# hot_air.net
KiCad netlist of a schematic drawn in Altium Designer
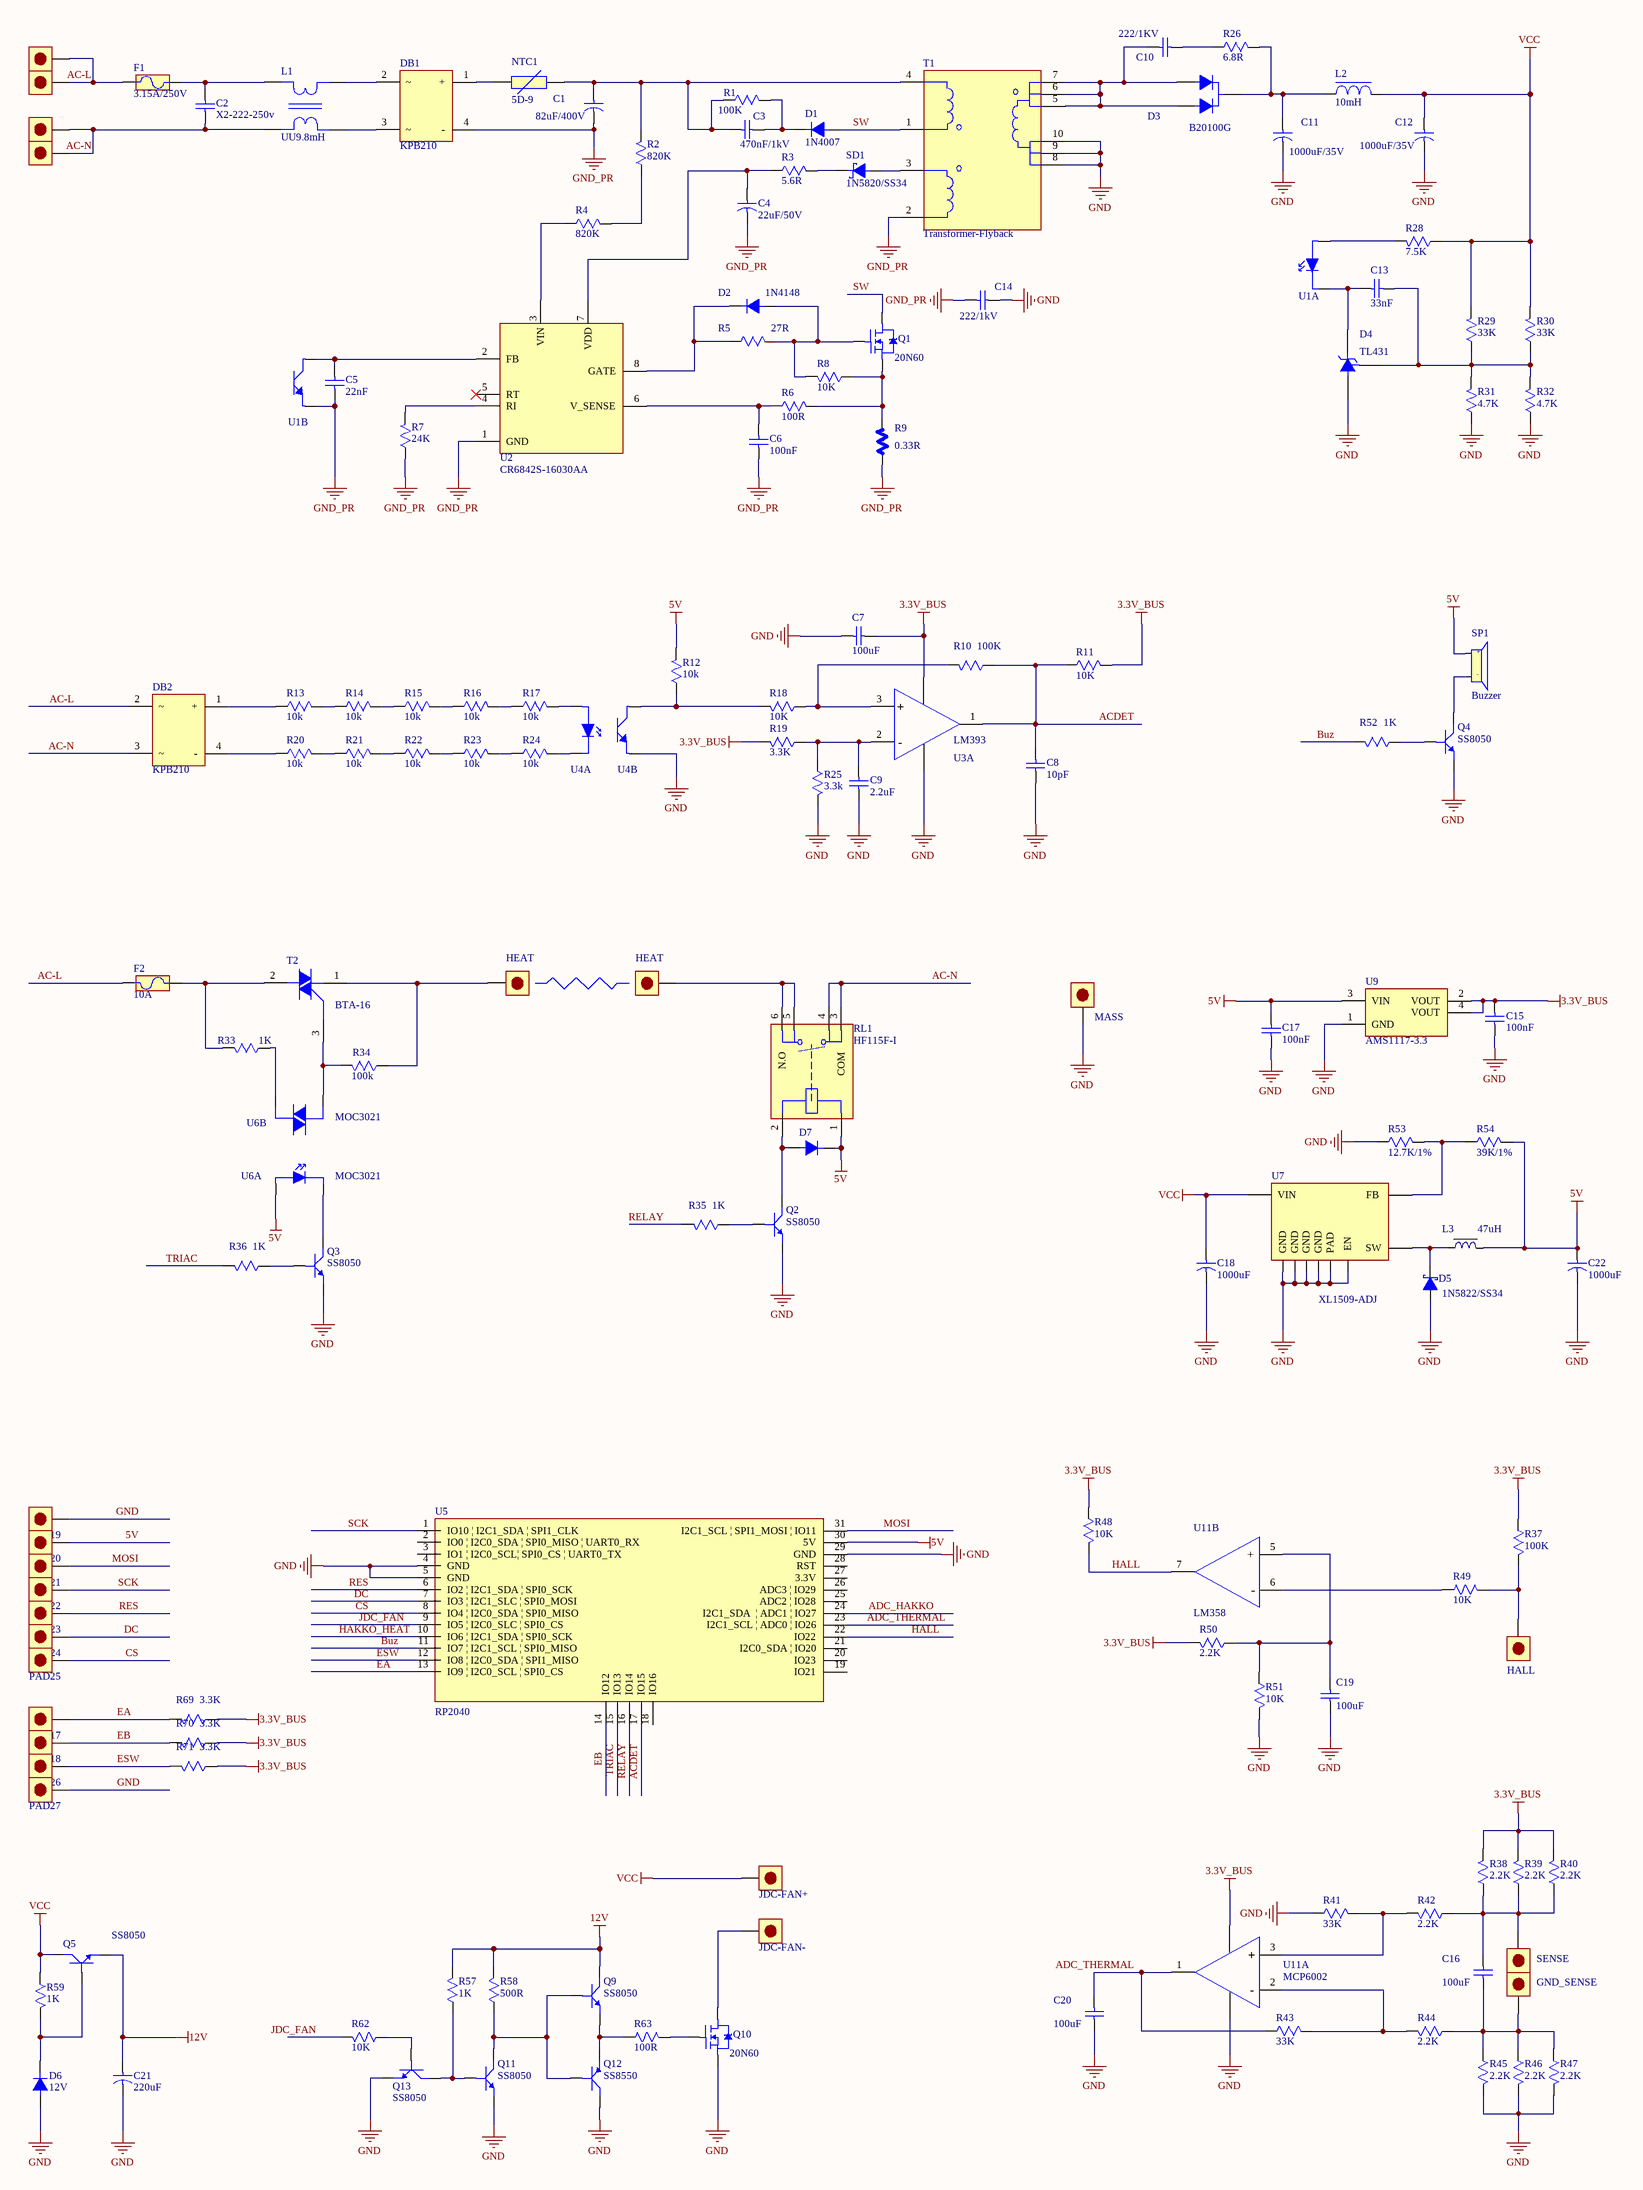
[diagram p0: hot_air.SchDoc]

(export (version "E")
  (design (tool "Eeschema 10.0.6"))
  (components
    (comp (ref "C1")
      (value "82uF/400V")
      (footprint "CAP-TH-16MM")
      (libsource (lib "Huan_basic") (part "Capacitor_polar"))
    )
    (comp (ref "C2")
      (value "X2-222-250v")
      (footprint "CAPACITOR-X2_10MM")
      (libsource (lib "Huan_basic") (part "Capacitor_non-polar"))
    )
    (comp (ref "C3")
      (value "470nF/1kV")
      (footprint "CAP-HV")
      (libsource (lib "Huan_basic") (part "Capacitor_non-polar"))
    )
    (comp (ref "C4")
      (value "22uF/50V")
      (footprint "CAP-TH-6.3MM")
      (libsource (lib "Huan_basic") (part "Capacitor_polar"))
    )
    (comp (ref "C5")
      (value "22nF")
      (footprint "C0805")
      (libsource (lib "Huan_basic") (part "Capacitor_non-polar"))
    )
    (comp (ref "C6")
      (value "100nF")
      (footprint "C0805")
      (libsource (lib "Huan_basic") (part "Capacitor_non-polar"))
    )
    (comp (ref "C7")
      (value "100uF")
      (footprint "C0805")
      (libsource (lib "Huan_basic") (part "Capacitor_non-polar"))
    )
    (comp (ref "C8")
      (value "10pF")
      (footprint "C0805")
      (libsource (lib "Huan_basic") (part "Capacitor_non-polar"))
    )
    (comp (ref "C9")
      (value "2.2uF")
      (footprint "C0805")
      (libsource (lib "Huan_basic") (part "Capacitor_non-polar"))
    )
    (comp (ref "C10")
      (value "222/1KV")
      (footprint "CAP-HV")
      (libsource (lib "Huan_basic") (part "Capacitor_non-polar"))
    )
    (comp (ref "C11")
      (value "1000uF/35V")
      (footprint "CAP-TH-10MM")
      (libsource (lib "Huan_basic") (part "Capacitor_polar"))
    )
    (comp (ref "C12")
      (value "1000uF/35V")
      (footprint "CAP-TH-10MM")
      (libsource (lib "Huan_basic") (part "Capacitor_polar"))
    )
    (comp (ref "C13")
      (value "33nF")
      (footprint "C0805")
      (libsource (lib "Huan_basic") (part "Capacitor_non-polar"))
    )
    (comp (ref "C14")
      (value "222/1kV")
      (footprint "CAP-HV")
      (libsource (lib "Huan_basic") (part "Capacitor_non-polar"))
    )
    (comp (ref "C15")
      (value "100nF")
      (footprint "C0805")
      (libsource (lib "Huan_basic") (part "Capacitor_non-polar"))
    )
    (comp (ref "C16")
      (value "100uF")
      (footprint "C0805")
      (libsource (lib "Huan_basic") (part "Capacitor_non-polar"))
    )
    (comp (ref "C17")
      (value "100nF")
      (footprint "C1206")
      (libsource (lib "Huan_basic") (part "Capacitor_non-polar"))
    )
    (comp (ref "C18")
      (value "1000uF")
      (footprint "CAP-TH-8MM")
      (libsource (lib "Huan_basic") (part "Capacitor_polar"))
    )
    (comp (ref "C19")
      (value "100uF")
      (footprint "C0805")
      (libsource (lib "Huan_basic") (part "Capacitor_non-polar"))
    )
    (comp (ref "C20")
      (value "100uF")
      (footprint "C0805")
      (libsource (lib "Huan_basic") (part "Capacitor_non-polar"))
    )
    (comp (ref "C21")
      (value "220uF")
      (footprint "CAP-TH-10MM")
      (libsource (lib "Huan_basic") (part "Capacitor_polar"))
    )
    (comp (ref "C22")
      (value "1000uF")
      (footprint "CAP-TH-8MM")
      (libsource (lib "Huan_basic") (part "Capacitor_polar"))
    )
    (comp (ref "D1")
      (value "1N4007")
      (footprint "DIODE/POW/1A")
      (libsource (lib "Huan_basic") (part "Diode"))
    )
    (comp (ref "D2")
      (value "1N4148")
      (footprint "LL-34(MiniMELF)")
      (libsource (lib "Huan_basic") (part "Diode"))
    )
    (comp (ref "D3") (value "B20100G") (footprint "TO-220") (libsource (lib "Huan_basic") (part "Diode-HC")))
    (comp (ref "D4") (value "TL431") (footprint "SOT-23") (libsource (lib "Huan_basic") (part "TL431")))
    (comp (ref "D5")
      (value "1N5822/SS34")
      (footprint "DO-214AC(SMA)")
      (description "Diode  Schottky")
      (libsource (lib "Sang_Library") (part "Diode  Schottky"))
    )
    (comp (ref "D6") (value "12V") (footprint "DO-41_V") (libsource (lib "Huan_basic") (part "Diode")))
    (comp (ref "D7") (value "~") (footprint "SOD-123F") (libsource (lib "Huan_basic") (part "Diode")))
    (comp (ref "DB1") (value "KPB210") (footprint "KBP210") (libsource (lib "Huan_basic") (part "H-Bridge")))
    (comp (ref "DB2") (value "KPB210") (footprint "ABS210") (libsource (lib "Huan_basic") (part "H-Bridge")))
    (comp (ref "F1")
      (value "3.15A/250V")
      (footprint "FUSE-3.15A-250V")
      (libsource (lib "Huan_basic") (part "FUSE"))
    )
    (comp (ref "F2") (value "10A") (footprint "FUSE-TH-5*20") (libsource (lib "") (part "FUSE_1")))
    (comp (ref "L1")
      (value "UU9.8mH")
      (footprint "UU9.8-7X8MM")
      (libsource (lib "Huan_basic") (part "Inductor-AC"))
    )
    (comp (ref "L2")
      (value "10mH")
      (footprint "INDUCTOR-TH-8mm")
      (libsource (lib "Huan_basic") (part "Inductor"))
    )
    (comp (ref "L3")
      (value "47uH")
      (footprint "L-SMD-06030-7.4x6.6X3")
      (description "inductor-SMD")
      (libsource (lib "Sang_Library") (part "inductor-SMD"))
    )
    (comp (ref "NTC1") (value "5D-9") (footprint "XD-13") (libsource (lib "Huan") (part "NTC")))
    (comp (ref "PAD1")
      (value "Pad_Through_Hole")
      (footprint "THROUGH_HOLE_MEDIUM")
      (libsource (lib "") (part "Pad_Through_Hole_2"))
    )
    (comp (ref "PAD2")
      (value "Pad_Through_Hole")
      (footprint "THROUGH_HOLE_MEDIUM")
      (libsource (lib "") (part "Pad_Through_Hole_2"))
    )
    (comp (ref "PAD3")
      (value "Pad_Through_Hole")
      (footprint "THROUGH_HOLE_MEDIUM")
      (libsource (lib "") (part "Pad_Through_Hole_2"))
    )
    (comp (ref "PAD4")
      (value "Pad_Through_Hole")
      (footprint "THROUGH_HOLE_MEDIUM")
      (libsource (lib "") (part "Pad_Through_Hole_2"))
    )
    (comp (ref "PAD5")
      (value "HEAT")
      (footprint "THROUGH_HOLE_MEDIUM")
      (libsource (lib "") (part "Pad_Through_Hole_2"))
    )
    (comp (ref "PAD6")
      (value "HEAT")
      (footprint "THROUGH_HOLE_MEDIUM")
      (libsource (lib "") (part "Pad_Through_Hole_1"))
    )
    (comp (ref "PAD7")
      (value "MASS")
      (footprint "THROUGH_HOLE_MEDIUM")
      (libsource (lib "") (part "Pad_Through_Hole_1"))
    )
    (comp (ref "PAD10")
      (value "HALL")
      (footprint "THROUGH_HOLE_MEDIUM")
      (libsource (lib "") (part "Pad_Through_Hole_2"))
    )
    (comp (ref "PAD11")
      (value "GND_SENSE")
      (footprint "THROUGH_HOLE_MEDIUM")
      (libsource (lib "") (part "Pad_Through_Hole_1"))
    )
    (comp (ref "PAD12")
      (value "SENSE")
      (footprint "THROUGH_HOLE_MEDIUM")
      (libsource (lib "Huan_basic") (part "Pad_Through_Hole"))
    )
    (comp (ref "PAD13")
      (value "JDC-FAN+")
      (footprint "THROUGH_HOLE_MEDIUM")
      (libsource (lib "") (part "Pad_Through_Hole_3"))
    )
    (comp (ref "PAD14")
      (value "JDC-FAN-")
      (footprint "THROUGH_HOLE_MEDIUM")
      (libsource (lib "") (part "Pad_Through_Hole_3"))
    )
    (comp (ref "PAD17")
      (value "Pad_Through_Hole")
      (footprint "THROUGH_HOLE_SMALL")
      (libsource (lib "Huan_basic") (part "Pad_Through_Hole"))
    )
    (comp (ref "PAD18")
      (value "Pad_Through_Hole")
      (footprint "THROUGH_HOLE_SMALL")
      (libsource (lib "Huan_basic") (part "Pad_Through_Hole"))
    )
    (comp (ref "PAD19")
      (value "Pad_Through_Hole")
      (footprint "THROUGH_HOLE_SMALL")
      (libsource (lib "Huan_basic") (part "Pad_Through_Hole"))
    )
    (comp (ref "PAD20")
      (value "Pad_Through_Hole")
      (footprint "THROUGH_HOLE_SMALL")
      (libsource (lib "Huan_basic") (part "Pad_Through_Hole"))
    )
    (comp (ref "PAD21")
      (value "Pad_Through_Hole")
      (footprint "THROUGH_HOLE_SMALL")
      (libsource (lib "Huan_basic") (part "Pad_Through_Hole"))
    )
    (comp (ref "PAD22")
      (value "Pad_Through_Hole")
      (footprint "THROUGH_HOLE_SMALL")
      (libsource (lib "Huan_basic") (part "Pad_Through_Hole"))
    )
    (comp (ref "PAD23")
      (value "Pad_Through_Hole")
      (footprint "THROUGH_HOLE_SMALL")
      (libsource (lib "Huan_basic") (part "Pad_Through_Hole"))
    )
    (comp (ref "PAD24")
      (value "Pad_Through_Hole")
      (footprint "THROUGH_HOLE_SMALL")
      (libsource (lib "Huan_basic") (part "Pad_Through_Hole"))
    )
    (comp (ref "PAD25")
      (value "Pad_Through_Hole")
      (footprint "THROUGH_HOLE_SMALL")
      (libsource (lib "Huan_basic") (part "Pad_Through_Hole"))
    )
    (comp (ref "PAD26")
      (value "Pad_Through_Hole")
      (footprint "THROUGH_HOLE_SMALL")
      (libsource (lib "Huan_basic") (part "Pad_Through_Hole"))
    )
    (comp (ref "PAD27")
      (value "Pad_Through_Hole")
      (footprint "THROUGH_HOLE_SMALL")
      (libsource (lib "Huan_basic") (part "Pad_Through_Hole"))
    )
    (comp (ref "Q1")
      (value "20N60")
      (footprint "TO-220")
      (libsource (lib "Huan_basic") (part "MOSFET_N-Chanel"))
    )
    (comp (ref "Q2")
      (value "SS8050")
      (footprint "SOT-23")
      (libsource (lib "Huan_basic") (part "Transistor-NPN"))
    )
    (comp (ref "Q3")
      (value "SS8050")
      (footprint "SOT-23")
      (libsource (lib "Huan_basic") (part "Transistor-NPN"))
    )
    (comp (ref "Q4")
      (value "SS8050")
      (footprint "SOT-23")
      (libsource (lib "Huan_basic") (part "Transistor-NPN"))
    )
    (comp (ref "Q5")
      (value "SS8050")
      (footprint "SOT-23")
      (libsource (lib "Huan_basic") (part "Transistor-NPN"))
    )
    (comp (ref "Q9")
      (value "SS8050")
      (footprint "SOT-23")
      (libsource (lib "Huan_basic") (part "Transistor-NPN"))
    )
    (comp (ref "Q10")
      (value "20N60")
      (footprint "TO-252-2")
      (libsource (lib "Huan_basic") (part "MOSFET_N-Chanel"))
    )
    (comp (ref "Q11")
      (value "SS8050")
      (footprint "SOT-23")
      (libsource (lib "Huan_basic") (part "Transistor-NPN"))
    )
    (comp (ref "Q12")
      (value "SS8550")
      (footprint "SOT-23")
      (libsource (lib "Huan_basic") (part "Transistor-PNP"))
    )
    (comp (ref "Q13")
      (value "SS8050")
      (footprint "SOT-23")
      (libsource (lib "Huan_basic") (part "Transistor-NPN"))
    )
    (comp (ref "R1") (value "100K") (footprint "R2512") (libsource (lib "Huan_basic") (part "Resistor")))
    (comp (ref "R2") (value "820K") (footprint "R0805") (libsource (lib "Huan_basic") (part "Resistor")))
    (comp (ref "R3") (value "5.6R") (footprint "R0805") (libsource (lib "Huan_basic") (part "Resistor")))
    (comp (ref "R4") (value "820K") (footprint "R0805") (libsource (lib "Huan_basic") (part "Resistor")))
    (comp (ref "R5") (value "27R") (footprint "R0805") (libsource (lib "Huan_basic") (part "Resistor")))
    (comp (ref "R6") (value "100R") (footprint "R0805") (libsource (lib "Huan_basic") (part "Resistor")))
    (comp (ref "R7") (value "24K") (footprint "R0805") (libsource (lib "Huan_basic") (part "Resistor")))
    (comp (ref "R8") (value "10K") (footprint "R0805") (libsource (lib "Huan_basic") (part "Resistor")))
    (comp (ref "R9")
      (value "0.33R")
      (footprint "R2512")
      (libsource (lib "Huan_basic") (part "Resistor_Shunt"))
    )
    (comp (ref "R10") (value "100K") (footprint "R0805") (libsource (lib "Huan_basic") (part "Resistor")))
    (comp (ref "R11") (value "10K") (footprint "R0805") (libsource (lib "Huan_basic") (part "Resistor")))
    (comp (ref "R12") (value "10k") (footprint "R0805") (libsource (lib "Huan_basic") (part "Resistor")))
    (comp (ref "R13") (value "10k") (footprint "R0805") (libsource (lib "Huan_basic") (part "Resistor")))
    (comp (ref "R14") (value "10k") (footprint "R0805") (libsource (lib "Huan_basic") (part "Resistor")))
    (comp (ref "R15") (value "10k") (footprint "R0805") (libsource (lib "Huan_basic") (part "Resistor")))
    (comp (ref "R16") (value "10k") (footprint "R0805") (libsource (lib "Huan_basic") (part "Resistor")))
    (comp (ref "R17") (value "10k") (footprint "R0805") (libsource (lib "Huan_basic") (part "Resistor")))
    (comp (ref "R18") (value "10K") (footprint "R0805") (libsource (lib "Huan_basic") (part "Resistor")))
    (comp (ref "R19") (value "3.3K") (footprint "R0805") (libsource (lib "Huan_basic") (part "Resistor")))
    (comp (ref "R20") (value "10k") (footprint "R0805") (libsource (lib "Huan_basic") (part "Resistor")))
    (comp (ref "R21") (value "10k") (footprint "R0805") (libsource (lib "Huan_basic") (part "Resistor")))
    (comp (ref "R22") (value "10k") (footprint "R0805") (libsource (lib "Huan_basic") (part "Resistor")))
    (comp (ref "R23") (value "10k") (footprint "R0805") (libsource (lib "Huan_basic") (part "Resistor")))
    (comp (ref "R24") (value "10k") (footprint "R0805") (libsource (lib "Huan_basic") (part "Resistor")))
    (comp (ref "R25") (value "3.3k") (footprint "R0805") (libsource (lib "Huan_basic") (part "Resistor")))
    (comp (ref "R26") (value "6.8R") (footprint "R0805") (libsource (lib "Huan_basic") (part "Resistor")))
    (comp (ref "R28") (value "7.5K") (footprint "R0805") (libsource (lib "Huan_basic") (part "Resistor")))
    (comp (ref "R29") (value "33K") (footprint "R0805") (libsource (lib "Huan_basic") (part "Resistor")))
    (comp (ref "R30") (value "33K") (footprint "R0805") (libsource (lib "Huan_basic") (part "Resistor")))
    (comp (ref "R31") (value "4.7K") (footprint "R0805") (libsource (lib "Huan_basic") (part "Resistor")))
    (comp (ref "R32") (value "4.7K") (footprint "R0805") (libsource (lib "Huan_basic") (part "Resistor")))
    (comp (ref "R33") (value "1K") (footprint "R2512") (libsource (lib "Huan_basic") (part "Resistor")))
    (comp (ref "R34") (value "100k") (footprint "R0805") (libsource (lib "Huan_basic") (part "Resistor")))
    (comp (ref "R35") (value "1K") (footprint "R0805") (libsource (lib "Huan_basic") (part "Resistor")))
    (comp (ref "R36") (value "1K") (footprint "R0805") (libsource (lib "Huan_basic") (part "Resistor")))
    (comp (ref "R37") (value "100K") (footprint "R0805") (libsource (lib "Huan_basic") (part "Resistor")))
    (comp (ref "R38") (value "2.2K") (footprint "R0805") (libsource (lib "Huan_basic") (part "Resistor")))
    (comp (ref "R39") (value "2.2K") (footprint "R0805") (libsource (lib "Huan_basic") (part "Resistor")))
    (comp (ref "R40") (value "2.2K") (footprint "R0805") (libsource (lib "Huan_basic") (part "Resistor")))
    (comp (ref "R41") (value "33K") (footprint "R0805") (libsource (lib "Huan_basic") (part "Resistor")))
    (comp (ref "R42") (value "2.2K") (footprint "R0805") (libsource (lib "Huan_basic") (part "Resistor")))
    (comp (ref "R43") (value "33K") (footprint "R0805") (libsource (lib "Huan_basic") (part "Resistor")))
    (comp (ref "R44") (value "2.2K") (footprint "R0805") (libsource (lib "Huan_basic") (part "Resistor")))
    (comp (ref "R45") (value "2.2K") (footprint "R0805") (libsource (lib "Huan_basic") (part "Resistor")))
    (comp (ref "R46") (value "2.2K") (footprint "R0805") (libsource (lib "Huan_basic") (part "Resistor")))
    (comp (ref "R47") (value "2.2K") (footprint "R0805") (libsource (lib "Huan_basic") (part "Resistor")))
    (comp (ref "R48") (value "10K") (footprint "R0805") (libsource (lib "Huan_basic") (part "Resistor")))
    (comp (ref "R49") (value "10K") (footprint "R0805") (libsource (lib "Huan_basic") (part "Resistor")))
    (comp (ref "R50") (value "2.2K") (footprint "R0805") (libsource (lib "Huan_basic") (part "Resistor")))
    (comp (ref "R51") (value "10K") (footprint "R0805") (libsource (lib "Huan_basic") (part "Resistor")))
    (comp (ref "R52") (value "1K") (footprint "R0805") (libsource (lib "Huan_basic") (part "Resistor")))
    (comp (ref "R53")
      (value "12.7K/1%")
      (footprint "R0603")
      (fields
        (field (name "MANUFACTURER") "Stackpole Electronics")
        (field (name "MANUFACTURER PART NUMBER") "RMCF0402FT10K0")
        (field (name "TOLERANCE") "1%")
      )
      (libsource (lib "Hunonic") (part "RES"))
    )
    (comp (ref "R54")
      (value "39K/1%")
      (footprint "R0603")
      (fields
        (field (name "MANUFACTURER") "Stackpole Electronics")
        (field (name "MANUFACTURER PART NUMBER") "RMCF0402FT10K0")
        (field (name "TOLERANCE") "1%")
      )
      (libsource (lib "Hunonic") (part "RES"))
    )
    (comp (ref "R57") (value "1K") (footprint "R0805") (libsource (lib "Huan_basic") (part "Resistor")))
    (comp (ref "R58") (value "500R") (footprint "R0805") (libsource (lib "Huan_basic") (part "Resistor")))
    (comp (ref "R59") (value "1K") (footprint "R0805") (libsource (lib "Huan_basic") (part "Resistor")))
    (comp (ref "R62") (value "10K") (footprint "R0805") (libsource (lib "Huan_basic") (part "Resistor")))
    (comp (ref "R63") (value "100R") (footprint "R0805") (libsource (lib "Huan_basic") (part "Resistor")))
    (comp (ref "R69") (value "3.3K") (footprint "R0805") (libsource (lib "Huan_basic") (part "Resistor")))
    (comp (ref "R70") (value "3.3K") (footprint "R0805") (libsource (lib "Huan_basic") (part "Resistor")))
    (comp (ref "R71") (value "3.3K") (footprint "R0805") (libsource (lib "Huan_basic") (part "Resistor")))
    (comp (ref "RL1")
      (value "HF115F-I")
      (footprint "HF115F-I")
      (libsource (lib "Huan_basic") (part "Relay-NC"))
    )
    (comp (ref "SD1")
      (value "1N5820/SS34")
      (footprint "DO-214AC(SMA)")
      (libsource (lib "Huan_basic") (part "Diode_Schottky"))
    )
    (comp (ref "SP1") (value "Buzzer") (footprint "Buzzer") (libsource (lib "Huan") (part "Buzzer_5V")))
    (comp (ref "T1")
      (value "Transformer-Flyback")
      (footprint "EE.27")
      (libsource (lib "Huan_basic") (part "Transformer-Flyback"))
    )
    (comp (ref "T2") (value "BTA-16") (footprint "TO-220") (libsource (lib "huan_basic") (part "Triac")))
    (comp (ref "U1") (value "PC817") (footprint "SMD-4") (libsource (lib "Huan_basic") (part "PC817")))
    (comp (ref "U2")
      (value "CR6842S-16030AA")
      (footprint "SOP-8")
      (libsource (lib "Huan_basic") (part "CR6842S"))
    )
    (comp (ref "U3")
      (value "LM393")
      (footprint "SOP-8")
      (libsource (lib "Huan_basic") (part "Op-Amply/Comparator"))
    )
    (comp (ref "U4") (value "PC817") (footprint "PC817") (libsource (lib "Huan_basic") (part "PC817")))
    (comp (ref "U5")
      (value "RP2040")
      (footprint "RP2040-MICROPRO")
      (libsource (lib "Huan_basic") (part "ProMicro RP2040"))
    )
    (comp (ref "U6")
      (value "MOC3021")
      (footprint "DIP-6")
      (libsource (lib "Huan_basic") (part "Triac-Isolate"))
    )
    (comp (ref "U7")
      (value "XL1509-ADJ")
      (footprint "SOP-8-PAD")
      (libsource (lib "Huan_basic") (part "XL1509-BUCK"))
    )
    (comp (ref "U9")
      (value "AMS1117-3.3")
      (footprint "SOT223")
      (libsource (lib "Huan_basic") (part "AMS1117"))
    )
    (comp (ref "U11")
      (value "MCP6002")
      (footprint "DIP-8")
      (libsource (lib "Huan_basic") (part "Op-Amply/Comparator"))
    )
  )
  (nets
    (net (code "1") (name "/AC-L") (class "Default")
      (node (ref "DB2") (pin "2") (pinfunction "~_2") (pintype "passive"))
      (node (ref "F1") (pin "1") (pinfunction "1_1") (pintype "passive"))
      (node (ref "F2") (pin "1") (pinfunction "1_1") (pintype "passive"))
      (node (ref "PAD3") (pin "1") (pintype "passive"))
      (node (ref "PAD4") (pin "1") (pintype "passive"))
    )
    (net (code "2") (name "/AC-N") (class "Default")
      (node (ref "C2") (pin "2") (pinfunction "2_2") (pintype "passive"))
      (node (ref "DB2") (pin "3") (pinfunction "~_3") (pintype "passive"))
      (node (ref "L1") (pin "4") (pinfunction "4_4") (pintype "passive"))
      (node (ref "PAD1") (pin "1") (pintype "passive"))
      (node (ref "PAD2") (pin "1") (pintype "passive"))
      (node (ref "RL1") (pin "3") (pinfunction "COM_3") (pintype "passive"))
      (node (ref "RL1") (pin "4") (pintype "passive"))
    )
    (net (code "3") (name "/ACDET") (class "Default")
      (node (ref "C8") (pin "2") (pinfunction "2_2") (pintype "passive"))
      (node (ref "R10") (pin "1") (pinfunction "1_1") (pintype "passive"))
      (node (ref "R11") (pin "1") (pinfunction "1_1") (pintype "passive"))
      (node (ref "U3") (pin "1") (pinfunction "1_1") (pintype "passive"))
      (node (ref "U5") (pin "17") (pinfunction "IO15_17") (pintype "power_in"))
    )
    (net (code "4") (name "/ADC_HAKKO") (class "Default")
      (node (ref "U5") (pin "24") (pinfunction "I2C1_SDA__¦_ADC1_¦_IO27_24") (pintype "power_in"))
    )
    (net (code "5") (name "/ADC_THERMAL") (class "Default")
      (node (ref "C20") (pin "1") (pinfunction "1_1") (pintype "passive"))
      (node (ref "R43") (pin "1") (pinfunction "1_1") (pintype "passive"))
      (node (ref "U11") (pin "1") (pinfunction "1_1") (pintype "passive"))
      (node (ref "U5") (pin "23") (pinfunction "I2C1_SCL_¦_ADC0_¦_IO26_23") (pintype "power_in"))
    )
    (net (code "6") (name "/Buz") (class "Default")
      (node (ref "R52") (pin "2") (pinfunction "2_2") (pintype "passive"))
      (node (ref "U5") (pin "11") (pinfunction "IO7_¦_I2C1_SCL_¦_SPI0_MISO_11") (pintype "power_in"))
    )
    (net (code "7") (name "/CS") (class "Default")
      (node (ref "PAD25") (pin "1") (pintype "passive"))
      (node (ref "U5") (pin "8") (pinfunction "IO4_¦_I2C0_SDA_¦_SPI0_MISO_8") (pintype "power_in"))
    )
    (net (code "8") (name "/DC") (class "Default")
      (node (ref "PAD24") (pin "1") (pintype "passive"))
      (node (ref "U5") (pin "7") (pinfunction "IO3_¦_I2C1_SLC_¦_SPI0_MOSI_7") (pintype "power_in"))
    )
    (net (code "9") (name "/EA") (class "Default")
      (node (ref "PAD17") (pin "1") (pintype "passive"))
      (node (ref "R69") (pin "2") (pinfunction "2_2") (pintype "passive"))
      (node (ref "U5") (pin "13") (pinfunction "IO9_¦_I2C0_SCL_¦_SPI0_CS_13") (pintype "power_in"))
    )
    (net (code "10") (name "/EB") (class "Default")
      (node (ref "PAD18") (pin "1") (pintype "passive"))
      (node (ref "R70") (pin "2") (pinfunction "2_2") (pintype "passive"))
      (node (ref "U5") (pin "14") (pinfunction "IO12_14") (pintype "power_in"))
    )
    (net (code "11") (name "/ESW") (class "Default")
      (node (ref "PAD26") (pin "1") (pintype "passive"))
      (node (ref "R71") (pin "2") (pinfunction "2_2") (pintype "passive"))
      (node (ref "U5") (pin "12") (pinfunction "IO8_¦_I2C0_SDA_¦_SPI1_MISO_12") (pintype "power_in"))
    )
    (net (code "12") (name "/HAKKO_HEAT") (class "Default")
      (node (ref "U5") (pin "10") (pinfunction "IO6_¦_I2C1_SDA_¦_SPI0_SCK_10") (pintype "power_in"))
    )
    (net (code "13") (name "/HALL") (class "Default")
      (node (ref "R48") (pin "1") (pinfunction "1_1") (pintype "passive"))
      (node (ref "U11") (pin "7") (pinfunction "7_7") (pintype "passive"))
      (node (ref "U5") (pin "22") (pinfunction "IO22_22") (pintype "power_in"))
    )
    (net (code "14") (name "/JDC_FAN") (class "Default")
      (node (ref "R62") (pin "1") (pinfunction "1_1") (pintype "passive"))
      (node (ref "U5") (pin "9") (pinfunction "IO5_¦_I2C0_SLC_¦_SPI0_CS_9") (pintype "power_in"))
    )
    (net (code "15") (name "/MOSI") (class "Default")
      (node (ref "PAD21") (pin "1") (pintype "passive"))
      (node (ref "U5") (pin "31") (pinfunction "I2C1_SCL_¦_SPI1_MOSI_¦_IO11_31") (pintype "power_in"))
    )
    (net (code "16") (name "/RELAY") (class "Default")
      (node (ref "R35") (pin "2") (pinfunction "2_2") (pintype "passive"))
      (node (ref "U5") (pin "16") (pinfunction "IO14_16") (pintype "power_in"))
    )
    (net (code "17") (name "/RES") (class "Default")
      (node (ref "PAD23") (pin "1") (pintype "passive"))
      (node (ref "U5") (pin "6") (pinfunction "IO2_¦_I2C1_SDA_¦_SPI0_SCK_6") (pintype "power_in"))
    )
    (net (code "18") (name "/SCK") (class "Default")
      (node (ref "PAD22") (pin "1") (pintype "passive"))
      (node (ref "U5") (pin "1") (pinfunction "IO10_¦_I2C1_SDA_¦_SPI1_CLK_1") (pintype "power_in"))
    )
    (net (code "19") (name "/SW") (class "Default")
      (node (ref "D1") (pin "1") (pinfunction "A_1") (pintype "passive"))
      (node (ref "Q1") (pin "2") (pinfunction "D_2") (pintype "passive"))
      (node (ref "T1") (pin "1") (pinfunction "1_1") (pintype "passive"))
    )
    (net (code "20") (name "/TRIAC") (class "Default")
      (node (ref "R36") (pin "2") (pinfunction "2_2") (pintype "passive"))
      (node (ref "U5") (pin "15") (pinfunction "IO13_15") (pintype "power_in"))
    )
    (net (code "21") (name "3.3V_BUS") (class "Default")
      (node (ref "C15") (pin "2") (pinfunction "2_2") (pintype "passive"))
      (node (ref "C7") (pin "1") (pinfunction "1_1") (pintype "passive"))
      (node (ref "R11") (pin "2") (pinfunction "2_2") (pintype "passive"))
      (node (ref "R19") (pin "2") (pinfunction "2_2") (pintype "passive"))
      (node (ref "R37") (pin "2") (pinfunction "2_2") (pintype "passive"))
      (node (ref "R38") (pin "2") (pinfunction "2_2") (pintype "passive"))
      (node (ref "R39") (pin "2") (pinfunction "2_2") (pintype "passive"))
      (node (ref "R40") (pin "2") (pinfunction "2_2") (pintype "passive"))
      (node (ref "R48") (pin "2") (pinfunction "2_2") (pintype "passive"))
      (node (ref "R50") (pin "2") (pinfunction "2_2") (pintype "passive"))
      (node (ref "R69") (pin "1") (pinfunction "1_1") (pintype "passive"))
      (node (ref "R70") (pin "1") (pinfunction "1_1") (pintype "passive"))
      (node (ref "R71") (pin "1") (pinfunction "1_1") (pintype "passive"))
      (node (ref "U11") (pin "8") (pinfunction "8_8") (pintype "passive"))
      (node (ref "U3") (pin "8") (pinfunction "8_8") (pintype "passive"))
      (node (ref "U9") (pin "2") (pinfunction "VOUT_2") (pintype "passive"))
      (node (ref "U9") (pin "4") (pinfunction "VOUT_4") (pintype "passive"))
    )
    (net (code "22") (name "5V") (class "Default")
      (node (ref "C17") (pin "2") (pinfunction "2_2") (pintype "passive"))
      (node (ref "C22") (pin "1") (pinfunction "1_1") (pintype "passive"))
      (node (ref "D7") (pin "2") (pinfunction "K_2") (pintype "passive"))
      (node (ref "L3") (pin "2") (pinfunction "2_2") (pintype "passive"))
      (node (ref "PAD20") (pin "1") (pintype "passive"))
      (node (ref "R12") (pin "2") (pinfunction "2_2") (pintype "passive"))
      (node (ref "R54") (pin "2") (pinfunction "2_2") (pintype "passive"))
      (node (ref "RL1") (pin "1") (pintype "passive"))
      (node (ref "SP1") (pin "1") (pinfunction "1_1") (pintype "passive"))
      (node (ref "U5") (pin "30") (pinfunction "5V_30") (pintype "power_in"))
      (node (ref "U6") (pin "1") (pinfunction "A_1") (pintype "passive"))
      (node (ref "U9") (pin "3") (pinfunction "VIN_3") (pintype "passive"))
    )
    (net (code "23") (name "12V") (class "Default")
      (node (ref "C21") (pin "1") (pinfunction "1_1") (pintype "passive"))
      (node (ref "Q5") (pin "2") (pinfunction "E_2") (pintype "passive"))
      (node (ref "Q9") (pin "3") (pinfunction "C_3") (pintype "passive"))
      (node (ref "R57") (pin "1") (pinfunction "1_1") (pintype "passive"))
      (node (ref "R58") (pin "1") (pinfunction "1_1") (pintype "passive"))
    )
    (net (code "24") (name "GND") (class "Default")
      (node (ref "C11") (pin "2") (pinfunction "2_2") (pintype "passive"))
      (node (ref "C12") (pin "2") (pinfunction "2_2") (pintype "passive"))
      (node (ref "C14") (pin "2") (pinfunction "2_2") (pintype "passive"))
      (node (ref "C15") (pin "1") (pinfunction "1_1") (pintype "passive"))
      (node (ref "C17") (pin "1") (pinfunction "1_1") (pintype "passive"))
      (node (ref "C18") (pin "2") (pinfunction "2_2") (pintype "passive"))
      (node (ref "C19") (pin "2") (pinfunction "2_2") (pintype "passive"))
      (node (ref "C20") (pin "2") (pinfunction "2_2") (pintype "passive"))
      (node (ref "C21") (pin "2") (pinfunction "2_2") (pintype "passive"))
      (node (ref "C22") (pin "2") (pinfunction "2_2") (pintype "passive"))
      (node (ref "C7") (pin "2") (pinfunction "2_2") (pintype "passive"))
      (node (ref "C8") (pin "1") (pinfunction "1_1") (pintype "passive"))
      (node (ref "C9") (pin "2") (pinfunction "2_2") (pintype "passive"))
      (node (ref "D4") (pin "3") (pinfunction "K_3") (pintype "passive"))
      (node (ref "D5") (pin "A") (pinfunction "A_A") (pintype "passive"))
      (node (ref "D6") (pin "1") (pinfunction "A_1") (pintype "passive"))
      (node (ref "PAD19") (pin "1") (pintype "passive"))
      (node (ref "PAD27") (pin "1") (pintype "passive"))
      (node (ref "PAD7") (pin "1") (pintype "passive"))
      (node (ref "Q10") (pin "3") (pinfunction "S_3") (pintype "passive"))
      (node (ref "Q11") (pin "2") (pinfunction "E_2") (pintype "passive"))
      (node (ref "Q12") (pin "3") (pinfunction "C_3") (pintype "passive"))
      (node (ref "Q13") (pin "2") (pinfunction "E_2") (pintype "passive"))
      (node (ref "Q2") (pin "2") (pinfunction "E_2") (pintype "passive"))
      (node (ref "Q3") (pin "2") (pinfunction "E_2") (pintype "passive"))
      (node (ref "Q4") (pin "2") (pinfunction "E_2") (pintype "passive"))
      (node (ref "R25") (pin "2") (pinfunction "2_2") (pintype "passive"))
      (node (ref "R31") (pin "1") (pinfunction "1_1") (pintype "passive"))
      (node (ref "R32") (pin "1") (pinfunction "1_1") (pintype "passive"))
      (node (ref "R41") (pin "1") (pinfunction "1_1") (pintype "passive"))
      (node (ref "R45") (pin "2") (pinfunction "2_2") (pintype "passive"))
      (node (ref "R46") (pin "2") (pinfunction "2_2") (pintype "passive"))
      (node (ref "R47") (pin "2") (pinfunction "2_2") (pintype "passive"))
      (node (ref "R51") (pin "1") (pinfunction "1_1") (pintype "passive"))
      (node (ref "R53") (pin "1") (pinfunction "1_1") (pintype "passive"))
      (node (ref "T1") (pin "10") (pinfunction "10_10") (pintype "passive"))
      (node (ref "T1") (pin "8") (pinfunction "8_8") (pintype "passive"))
      (node (ref "T1") (pin "9") (pinfunction "9_9") (pintype "passive"))
      (node (ref "U11") (pin "4") (pinfunction "4_4") (pintype "passive"))
      (node (ref "U3") (pin "4") (pinfunction "4_4") (pintype "passive"))
      (node (ref "U4") (pin "3") (pinfunction "E_3") (pintype "passive"))
      (node (ref "U5") (pin "29") (pinfunction "GND_29") (pintype "power_in"))
      (node (ref "U5") (pin "4") (pinfunction "GND_4") (pintype "power_in"))
      (node (ref "U5") (pin "5") (pinfunction "GND_5") (pintype "power_in"))
      (node (ref "U7") (pin "4") (pinfunction "EN_4") (pintype "passive"))
      (node (ref "U7") (pin "5") (pinfunction "GND_5") (pintype "passive"))
      (node (ref "U7") (pin "6") (pinfunction "GND_6") (pintype "passive"))
      (node (ref "U7") (pin "7") (pinfunction "GND_7") (pintype "passive"))
      (node (ref "U7") (pin "8") (pinfunction "GND_8") (pintype "passive"))
      (node (ref "U7") (pin "9") (pinfunction "PAD_9") (pintype "passive"))
      (node (ref "U9") (pin "1") (pinfunction "GND_1") (pintype "passive"))
    )
    (net (code "25") (name "GND_PR") (class "Default")
      (node (ref "C1") (pin "2") (pinfunction "2_2") (pintype "passive"))
      (node (ref "C14") (pin "1") (pinfunction "1_1") (pintype "passive"))
      (node (ref "C4") (pin "2") (pinfunction "2_2") (pintype "passive"))
      (node (ref "C5") (pin "1") (pinfunction "1_1") (pintype "passive"))
      (node (ref "C6") (pin "1") (pinfunction "1_1") (pintype "passive"))
      (node (ref "DB1") (pin "4") (pinfunction "-_4") (pintype "passive"))
      (node (ref "R7") (pin "1") (pinfunction "1_1") (pintype "passive"))
      (node (ref "R9") (pin "1") (pinfunction "1_1") (pintype "passive"))
      (node (ref "T1") (pin "2") (pinfunction "2_2") (pintype "passive"))
      (node (ref "U1") (pin "3") (pinfunction "E_3") (pintype "passive"))
      (node (ref "U2") (pin "1") (pinfunction "GND_1") (pintype "passive"))
    )
    (net (code "26") (name "Net-(C1-Pad1)") (class "Default")
      (node (ref "C1") (pin "1") (pinfunction "1_1") (pintype "passive"))
      (node (ref "C3") (pin "2") (pinfunction "2_2") (pintype "passive"))
      (node (ref "NTC1") (pin "2") (pinfunction "2_2") (pintype "passive"))
      (node (ref "R1") (pin "1") (pinfunction "1_1") (pintype "passive"))
      (node (ref "R2") (pin "2") (pinfunction "2_2") (pintype "passive"))
      (node (ref "T1") (pin "4") (pinfunction "4_4") (pintype "passive"))
    )
    (net (code "27") (name "Net-(C2-Pad1)") (class "Default")
      (node (ref "C2") (pin "1") (pinfunction "1_1") (pintype "passive"))
      (node (ref "F1") (pin "2") (pinfunction "2_2") (pintype "passive"))
      (node (ref "L1") (pin "1") (pintype "passive"))
    )
    (net (code "28") (name "Net-(C10-Pad1)") (class "Default")
      (node (ref "C10") (pin "1") (pinfunction "1_1") (pintype "passive"))
      (node (ref "D3") (pin "1") (pinfunction "A_1") (pintype "passive"))
      (node (ref "D3") (pin "3") (pinfunction "A_3") (pintype "passive"))
      (node (ref "T1") (pin "5") (pinfunction "5_5") (pintype "passive"))
      (node (ref "T1") (pin "6") (pinfunction "6_6") (pintype "passive"))
      (node (ref "T1") (pin "7") (pinfunction "7_7") (pintype "passive"))
    )
    (net (code "29") (name "Net-(C10-Pad2)") (class "Default")
      (node (ref "C10") (pin "2") (pinfunction "2_2") (pintype "passive"))
      (node (ref "R26") (pin "1") (pinfunction "1_1") (pintype "passive"))
    )
    (net (code "30") (name "Net-(C16-Pad1)") (class "Default")
      (node (ref "C16") (pin "1") (pinfunction "1_1") (pintype "passive"))
      (node (ref "PAD12") (pin "1") (pintype "passive"))
      (node (ref "R38") (pin "1") (pinfunction "1_1") (pintype "passive"))
      (node (ref "R39") (pin "1") (pinfunction "1_1") (pintype "passive"))
      (node (ref "R40") (pin "1") (pinfunction "1_1") (pintype "passive"))
      (node (ref "R42") (pin "1") (pinfunction "1_1") (pintype "passive"))
    )
    (net (code "31") (name "Net-(C16-Pad2)") (class "Default")
      (node (ref "C16") (pin "2") (pinfunction "2_2") (pintype "passive"))
      (node (ref "PAD11") (pin "1") (pintype "passive"))
      (node (ref "R44") (pin "1") (pinfunction "1_1") (pintype "passive"))
      (node (ref "R45") (pin "1") (pinfunction "1_1") (pintype "passive"))
      (node (ref "R46") (pin "1") (pinfunction "1_1") (pintype "passive"))
      (node (ref "R47") (pin "1") (pinfunction "1_1") (pintype "passive"))
    )
    (net (code "32") (name "Net-(D1-K)") (class "Default")
      (node (ref "C3") (pin "1") (pinfunction "1_1") (pintype "passive"))
      (node (ref "D1") (pin "2") (pinfunction "K_2") (pintype "passive"))
      (node (ref "R1") (pin "2") (pinfunction "2_2") (pintype "passive"))
    )
    (net (code "33") (name "Net-(D2-A)") (class "Default")
      (node (ref "D2") (pin "1") (pinfunction "A_1") (pintype "passive"))
      (node (ref "Q1") (pin "1") (pinfunction "G_1") (pintype "passive"))
      (node (ref "R5") (pin "2") (pinfunction "2_2") (pintype "passive"))
      (node (ref "R8") (pin "2") (pinfunction "2_2") (pintype "passive"))
    )
    (net (code "34") (name "Net-(D2-K)") (class "Default")
      (node (ref "D2") (pin "2") (pinfunction "K_2") (pintype "passive"))
      (node (ref "R5") (pin "1") (pinfunction "1_1") (pintype "passive"))
      (node (ref "U2") (pin "8") (pinfunction "GATE_8") (pintype "passive"))
    )
    (net (code "35") (name "Net-(D3-K)") (class "Default")
      (node (ref "C11") (pin "1") (pinfunction "1_1") (pintype "passive"))
      (node (ref "D3") (pin "2") (pinfunction "K_2") (pintype "passive"))
      (node (ref "L2") (pin "1") (pintype "passive"))
      (node (ref "R26") (pin "2") (pinfunction "2_2") (pintype "passive"))
    )
    (net (code "36") (name "Net-(D4-A)") (class "Default")
      (node (ref "C13") (pin "1") (pinfunction "1_1") (pintype "passive"))
      (node (ref "D4") (pin "1") (pinfunction "A_1") (pintype "passive"))
      (node (ref "R29") (pin "1") (pinfunction "1_1") (pintype "passive"))
      (node (ref "R30") (pin "1") (pinfunction "1_1") (pintype "passive"))
      (node (ref "R31") (pin "2") (pinfunction "2_2") (pintype "passive"))
      (node (ref "R32") (pin "2") (pinfunction "2_2") (pintype "passive"))
    )
    (net (code "37") (name "Net-(D6-K)") (class "Default")
      (node (ref "D6") (pin "2") (pinfunction "K_2") (pintype "passive"))
      (node (ref "Q5") (pin "1") (pinfunction "B_1") (pintype "passive"))
      (node (ref "R59") (pin "2") (pinfunction "2_2") (pintype "passive"))
    )
    (net (code "38") (name "Net-(D7-A)") (class "Default")
      (node (ref "D7") (pin "1") (pinfunction "A_1") (pintype "passive"))
      (node (ref "Q2") (pin "3") (pinfunction "C_3") (pintype "passive"))
      (node (ref "RL1") (pin "2") (pintype "passive"))
    )
    (net (code "39") (name "Net-(DB1-+)") (class "Default")
      (node (ref "DB1") (pin "1") (pinfunction "+_1") (pintype "passive"))
      (node (ref "NTC1") (pin "1") (pinfunction "1_1") (pintype "passive"))
    )
    (net (code "40") (name "Net-(DB1-~-Pad2)") (class "Default")
      (node (ref "DB1") (pin "2") (pinfunction "~_2") (pintype "passive"))
      (node (ref "L1") (pin "2") (pintype "passive"))
    )
    (net (code "41") (name "Net-(DB1-~-Pad3)") (class "Default")
      (node (ref "DB1") (pin "3") (pinfunction "~_3") (pintype "passive"))
      (node (ref "L1") (pin "3") (pinfunction "3_3") (pintype "passive"))
    )
    (net (code "42") (name "Net-(DB2-+)") (class "Default")
      (node (ref "DB2") (pin "1") (pinfunction "+_1") (pintype "passive"))
      (node (ref "R13") (pin "1") (pinfunction "1_1") (pintype "passive"))
    )
    (net (code "43") (name "Net-(DB2--)") (class "Default")
      (node (ref "DB2") (pin "4") (pinfunction "-_4") (pintype "passive"))
      (node (ref "R20") (pin "1") (pinfunction "1_1") (pintype "passive"))
    )
    (net (code "44") (name "Net-(F2-Pad2)") (class "Default")
      (node (ref "F2") (pin "2") (pinfunction "2_2") (pintype "passive"))
      (node (ref "R33") (pin "2") (pinfunction "2_2") (pintype "passive"))
      (node (ref "T2") (pin "2") (pinfunction "A_2") (pintype "passive"))
    )
    (net (code "45") (name "Net-(PAD6-Pad1)") (class "Default")
      (node (ref "PAD6") (pin "1") (pintype "passive"))
      (node (ref "R34") (pin "1") (pinfunction "1_1") (pintype "passive"))
      (node (ref "T2") (pin "1") (pinfunction "A_1") (pintype "passive"))
    )
    (net (code "46") (name "Net-(PAD10-Pad1)") (class "Default")
      (node (ref "PAD10") (pin "1") (pintype "passive"))
      (node (ref "R37") (pin "1") (pinfunction "1_1") (pintype "passive"))
      (node (ref "R49") (pin "1") (pinfunction "1_1") (pintype "passive"))
    )
    (net (code "47") (name "Net-(Q1-S)") (class "Default")
      (node (ref "Q1") (pin "3") (pinfunction "S_3") (pintype "passive"))
      (node (ref "R6") (pin "2") (pinfunction "2_2") (pintype "passive"))
      (node (ref "R8") (pin "1") (pinfunction "1_1") (pintype "passive"))
      (node (ref "R9") (pin "2") (pinfunction "2_2") (pintype "passive"))
    )
    (net (code "48") (name "Net-(Q2-B)") (class "Default")
      (node (ref "Q2") (pin "1") (pinfunction "B_1") (pintype "passive"))
      (node (ref "R35") (pin "1") (pinfunction "1_1") (pintype "passive"))
    )
    (net (code "49") (name "Net-(Q3-B)") (class "Default")
      (node (ref "Q3") (pin "1") (pinfunction "B_1") (pintype "passive"))
      (node (ref "R36") (pin "1") (pinfunction "1_1") (pintype "passive"))
    )
    (net (code "50") (name "Net-(Q3-C)") (class "Default")
      (node (ref "Q3") (pin "3") (pinfunction "C_3") (pintype "passive"))
      (node (ref "U6") (pin "2") (pinfunction "K_2") (pintype "passive"))
    )
    (net (code "51") (name "Net-(Q4-B)") (class "Default")
      (node (ref "Q4") (pin "1") (pinfunction "B_1") (pintype "passive"))
      (node (ref "R52") (pin "1") (pinfunction "1_1") (pintype "passive"))
    )
    (net (code "52") (name "Net-(Q4-C)") (class "Default")
      (node (ref "Q4") (pin "3") (pinfunction "C_3") (pintype "passive"))
      (node (ref "SP1") (pin "2") (pinfunction "2_2") (pintype "passive"))
    )
    (net (code "53") (name "Net-(Q10-D)") (class "Default")
      (node (ref "PAD14") (pin "1") (pintype "passive"))
      (node (ref "Q10") (pin "2") (pinfunction "D_2") (pintype "passive"))
    )
    (net (code "54") (name "Net-(Q10-G)") (class "Default")
      (node (ref "Q10") (pin "1") (pinfunction "G_1") (pintype "passive"))
      (node (ref "R63") (pin "1") (pinfunction "1_1") (pintype "passive"))
    )
    (net (code "55") (name "Net-(Q11-B)") (class "Default")
      (node (ref "Q11") (pin "1") (pinfunction "B_1") (pintype "passive"))
      (node (ref "Q13") (pin "3") (pinfunction "C_3") (pintype "passive"))
      (node (ref "R57") (pin "2") (pinfunction "2_2") (pintype "passive"))
    )
    (net (code "56") (name "Net-(Q11-C)") (class "Default")
      (node (ref "Q11") (pin "3") (pinfunction "C_3") (pintype "passive"))
      (node (ref "Q12") (pin "1") (pinfunction "B_1") (pintype "passive"))
      (node (ref "Q9") (pin "1") (pinfunction "B_1") (pintype "passive"))
      (node (ref "R58") (pin "2") (pinfunction "2_2") (pintype "passive"))
    )
    (net (code "57") (name "Net-(Q12-E)") (class "Default")
      (node (ref "Q12") (pin "2") (pinfunction "E_2") (pintype "passive"))
      (node (ref "Q9") (pin "2") (pinfunction "E_2") (pintype "passive"))
      (node (ref "R63") (pin "2") (pinfunction "2_2") (pintype "passive"))
    )
    (net (code "58") (name "Net-(Q13-B)") (class "Default")
      (node (ref "Q13") (pin "1") (pinfunction "B_1") (pintype "passive"))
      (node (ref "R62") (pin "2") (pinfunction "2_2") (pintype "passive"))
    )
    (net (code "59") (name "Net-(R2-Pad1)") (class "Default")
      (node (ref "R2") (pin "1") (pinfunction "1_1") (pintype "passive"))
      (node (ref "R4") (pin "2") (pinfunction "2_2") (pintype "passive"))
    )
    (net (code "60") (name "Net-(R13-Pad2)") (class "Default")
      (node (ref "R13") (pin "2") (pinfunction "2_2") (pintype "passive"))
      (node (ref "R14") (pin "1") (pinfunction "1_1") (pintype "passive"))
    )
    (net (code "61") (name "Net-(R14-Pad2)") (class "Default")
      (node (ref "R14") (pin "2") (pinfunction "2_2") (pintype "passive"))
      (node (ref "R15") (pin "1") (pinfunction "1_1") (pintype "passive"))
    )
    (net (code "62") (name "Net-(R15-Pad2)") (class "Default")
      (node (ref "R15") (pin "2") (pinfunction "2_2") (pintype "passive"))
      (node (ref "R16") (pin "1") (pinfunction "1_1") (pintype "passive"))
    )
    (net (code "63") (name "Net-(R16-Pad2)") (class "Default")
      (node (ref "R16") (pin "2") (pinfunction "2_2") (pintype "passive"))
      (node (ref "R17") (pin "1") (pinfunction "1_1") (pintype "passive"))
    )
    (net (code "64") (name "Net-(R20-Pad2)") (class "Default")
      (node (ref "R20") (pin "2") (pinfunction "2_2") (pintype "passive"))
      (node (ref "R21") (pin "1") (pinfunction "1_1") (pintype "passive"))
    )
    (net (code "65") (name "Net-(R21-Pad2)") (class "Default")
      (node (ref "R21") (pin "2") (pinfunction "2_2") (pintype "passive"))
      (node (ref "R22") (pin "1") (pinfunction "1_1") (pintype "passive"))
    )
    (net (code "66") (name "Net-(R22-Pad2)") (class "Default")
      (node (ref "R22") (pin "2") (pinfunction "2_2") (pintype "passive"))
      (node (ref "R23") (pin "1") (pinfunction "1_1") (pintype "passive"))
    )
    (net (code "67") (name "Net-(R23-Pad2)") (class "Default")
      (node (ref "R23") (pin "2") (pinfunction "2_2") (pintype "passive"))
      (node (ref "R24") (pin "1") (pinfunction "1_1") (pintype "passive"))
    )
    (net (code "68") (name "Net-(R33-Pad1)") (class "Default")
      (node (ref "R33") (pin "1") (pinfunction "1_1") (pintype "passive"))
      (node (ref "U6") (pin "6") (pintype "passive"))
    )
    (net (code "69") (name "Net-(R34-Pad2)") (class "Default")
      (node (ref "R34") (pin "2") (pinfunction "2_2") (pintype "passive"))
      (node (ref "T2") (pin "3") (pinfunction "A_3") (pintype "passive"))
      (node (ref "U6") (pin "4") (pintype "passive"))
    )
    (net (code "70") (name "Net-(RL1-N.O)") (class "Default")
      (node (ref "PAD5") (pin "1") (pintype "passive"))
      (node (ref "RL1") (pin "5") (pintype "passive"))
      (node (ref "RL1") (pin "6") (pinfunction "N.O_6") (pintype "passive"))
    )
    (net (code "71") (name "Net-(SD1-A)") (class "Default")
      (node (ref "SD1") (pin "1") (pinfunction "A_1") (pintype "passive"))
      (node (ref "T1") (pin "3") (pinfunction "3_3") (pintype "passive"))
    )
    (net (code "72") (name "Net-(SD1-K)") (class "Default")
      (node (ref "R3") (pin "2") (pinfunction "2_2") (pintype "passive"))
      (node (ref "SD1") (pin "2") (pinfunction "K_2") (pintype "passive"))
    )
    (net (code "73") (name "Net-(U1A-A)") (class "Default")
      (node (ref "R28") (pin "2") (pinfunction "2_2") (pintype "passive"))
      (node (ref "U1") (pin "1") (pinfunction "A_1") (pintype "passive"))
    )
    (net (code "74") (name "Net-(U1A-K)") (class "Default")
      (node (ref "C13") (pin "2") (pinfunction "2_2") (pintype "passive"))
      (node (ref "D4") (pin "2") (pinfunction "K_2") (pintype "passive"))
      (node (ref "U1") (pin "2") (pinfunction "K_2") (pintype "passive"))
    )
    (net (code "75") (name "Net-(U1B-C)") (class "Default")
      (node (ref "C5") (pin "2") (pinfunction "2_2") (pintype "passive"))
      (node (ref "U1") (pin "4") (pinfunction "C_4") (pintype "passive"))
      (node (ref "U2") (pin "2") (pinfunction "FB_2") (pintype "passive"))
    )
    (net (code "76") (name "Net-(U2-RI)") (class "Default")
      (node (ref "R7") (pin "2") (pinfunction "2_2") (pintype "passive"))
      (node (ref "U2") (pin "4") (pinfunction "RI_4") (pintype "passive"))
    )
    (net (code "77") (name "Net-(U2-VDD)") (class "Default")
      (node (ref "C4") (pin "1") (pinfunction "1_1") (pintype "passive"))
      (node (ref "R3") (pin "1") (pinfunction "1_1") (pintype "passive"))
      (node (ref "U2") (pin "7") (pinfunction "VDD_7") (pintype "passive"))
    )
    (net (code "78") (name "Net-(U2-VIN)") (class "Default")
      (node (ref "R4") (pin "1") (pinfunction "1_1") (pintype "passive"))
      (node (ref "U2") (pin "3") (pinfunction "VIN_3") (pintype "passive"))
    )
    (net (code "79") (name "Net-(U2-V_SENSE)") (class "Default")
      (node (ref "C6") (pin "2") (pinfunction "2_2") (pintype "passive"))
      (node (ref "R6") (pin "1") (pinfunction "1_1") (pintype "passive"))
      (node (ref "U2") (pin "6") (pinfunction "V_SENSE_6") (pintype "passive"))
    )
    (net (code "80") (name "Net-(U3A-+)") (class "Default")
      (node (ref "R10") (pin "2") (pinfunction "2_2") (pintype "passive"))
      (node (ref "R18") (pin "1") (pinfunction "1_1") (pintype "passive"))
      (node (ref "U3") (pin "3") (pinfunction "+_3") (pintype "passive"))
    )
    (net (code "81") (name "Net-(U3A--)") (class "Default")
      (node (ref "C9") (pin "1") (pinfunction "1_1") (pintype "passive"))
      (node (ref "R19") (pin "1") (pinfunction "1_1") (pintype "passive"))
      (node (ref "R25") (pin "1") (pinfunction "1_1") (pintype "passive"))
      (node (ref "U3") (pin "2") (pinfunction "-_2") (pintype "passive"))
    )
    (net (code "82") (name "Net-(U4A-A)") (class "Default")
      (node (ref "R17") (pin "2") (pinfunction "2_2") (pintype "passive"))
      (node (ref "U4") (pin "1") (pinfunction "A_1") (pintype "passive"))
    )
    (net (code "83") (name "Net-(U4A-K)") (class "Default")
      (node (ref "R24") (pin "2") (pinfunction "2_2") (pintype "passive"))
      (node (ref "U4") (pin "2") (pinfunction "K_2") (pintype "passive"))
    )
    (net (code "84") (name "Net-(U4B-C)") (class "Default")
      (node (ref "R12") (pin "1") (pinfunction "1_1") (pintype "passive"))
      (node (ref "R18") (pin "2") (pinfunction "2_2") (pintype "passive"))
      (node (ref "U4") (pin "4") (pinfunction "C_4") (pintype "passive"))
    )
    (net (code "85") (name "Net-(U7-FB)") (class "Default")
      (node (ref "R53") (pin "2") (pinfunction "2_2") (pintype "passive"))
      (node (ref "R54") (pin "1") (pinfunction "1_1") (pintype "passive"))
      (node (ref "U7") (pin "3") (pinfunction "FB_3") (pintype "passive"))
    )
    (net (code "86") (name "Net-(U7-SW)") (class "Default")
      (node (ref "D5") (pin "K") (pinfunction "K_K") (pintype "passive"))
      (node (ref "L3") (pin "1") (pinfunction "1_1") (pintype "passive"))
      (node (ref "U7") (pin "2") (pinfunction "SW_2") (pintype "passive"))
    )
    (net (code "87") (name "Net-(U11A-+)") (class "Default")
      (node (ref "R41") (pin "2") (pinfunction "2_2") (pintype "passive"))
      (node (ref "R42") (pin "2") (pinfunction "2_2") (pintype "passive"))
      (node (ref "U11") (pin "3") (pinfunction "+_3") (pintype "passive"))
    )
    (net (code "88") (name "Net-(U11A--)") (class "Default")
      (node (ref "R43") (pin "2") (pinfunction "2_2") (pintype "passive"))
      (node (ref "R44") (pin "2") (pinfunction "2_2") (pintype "passive"))
      (node (ref "U11") (pin "2") (pinfunction "-_2") (pintype "passive"))
    )
    (net (code "89") (name "Net-(U11B-+)") (class "Default")
      (node (ref "C19") (pin "1") (pinfunction "1_1") (pintype "passive"))
      (node (ref "R50") (pin "1") (pinfunction "1_1") (pintype "passive"))
      (node (ref "R51") (pin "2") (pinfunction "2_2") (pintype "passive"))
      (node (ref "U11") (pin "5") (pinfunction "+_5") (pintype "passive"))
    )
    (net (code "90") (name "Net-(U11B--)") (class "Default")
      (node (ref "R49") (pin "2") (pinfunction "2_2") (pintype "passive"))
      (node (ref "U11") (pin "6") (pinfunction "-_6") (pintype "passive"))
    )
    (net (code "91") (name "VCC") (class "Default")
      (node (ref "C12") (pin "1") (pinfunction "1_1") (pintype "passive"))
      (node (ref "C18") (pin "1") (pinfunction "1_1") (pintype "passive"))
      (node (ref "L2") (pin "2") (pintype "passive"))
      (node (ref "PAD13") (pin "1") (pintype "passive"))
      (node (ref "Q5") (pin "3") (pinfunction "C_3") (pintype "passive"))
      (node (ref "R28") (pin "1") (pinfunction "1_1") (pintype "passive"))
      (node (ref "R29") (pin "2") (pinfunction "2_2") (pintype "passive"))
      (node (ref "R30") (pin "2") (pinfunction "2_2") (pintype "passive"))
      (node (ref "R59") (pin "1") (pinfunction "1_1") (pintype "passive"))
      (node (ref "U7") (pin "1") (pinfunction "VIN_1") (pintype "passive"))
    )
    (net (code "92") (name "unconnected-(U2-RT-Pad5)") (class "Default")
      (node (ref "U2") (pin "5") (pinfunction "RT_5") (pintype "passive+no_connect"))
    )
    (net (code "93") (name "unconnected-(U5-3.3V-Pad27)") (class "Default")
      (node (ref "U5") (pin "27") (pinfunction "3.3V_27") (pintype "power_in"))
    )
    (net (code "94") (name "unconnected-(U5-ADC2_¦_IO28-Pad25)") (class "Default")
      (node (ref "U5") (pin "25") (pinfunction "ADC2_¦_IO28_25") (pintype "power_in"))
    )
    (net (code "95") (name "unconnected-(U5-ADC3_¦_IO29-Pad26)") (class "Default")
      (node (ref "U5") (pin "26") (pinfunction "ADC3_¦_IO29_26") (pintype "power_in"))
    )
    (net (code "96") (name "unconnected-(U5-I2C0_SDA_¦_IO20-Pad21)") (class "Default")
      (node (ref "U5") (pin "21") (pinfunction "I2C0_SDA_¦_IO20_21") (pintype "power_in"))
    )
    (net (code "97") (name "unconnected-(U5-IO0_¦_I2C0_SDA_¦_SPI0_MISO_¦_UART0_RX-Pad2)") (class "Default")
      (node (ref "U5") (pin "2") (pinfunction "IO0_¦_I2C0_SDA_¦_SPI0_MISO_¦_UART0_RX_2") (pintype "power_in"))
    )
    (net (code "98") (name "unconnected-(U5-IO1_¦_I2C0_SCL¦_SPI0_CS_¦_UART0_TX-Pad3)") (class "Default")
      (node (ref "U5") (pin "3") (pinfunction "IO1_¦_I2C0_SCL¦_SPI0_CS_¦_UART0_TX_3") (pintype "power_in"))
    )
    (net (code "99") (name "unconnected-(U5-IO16-Pad18)") (class "Default")
      (node (ref "U5") (pin "18") (pinfunction "IO16_18") (pintype "power_in"))
    )
    (net (code "100") (name "unconnected-(U5-IO21-Pad19)") (class "Default")
      (node (ref "U5") (pin "19") (pinfunction "IO21_19") (pintype "power_in"))
    )
    (net (code "101") (name "unconnected-(U5-IO23-Pad20)") (class "Default")
      (node (ref "U5") (pin "20") (pinfunction "IO23_20") (pintype "power_in"))
    )
    (net (code "102") (name "unconnected-(U5-RST-Pad28)") (class "Default")
      (node (ref "U5") (pin "28") (pinfunction "RST_28") (pintype "power_in"))
    )
  )
)
